# DcDc3V3.net
KiCad netlist of a schematic drawn in Altium Designer
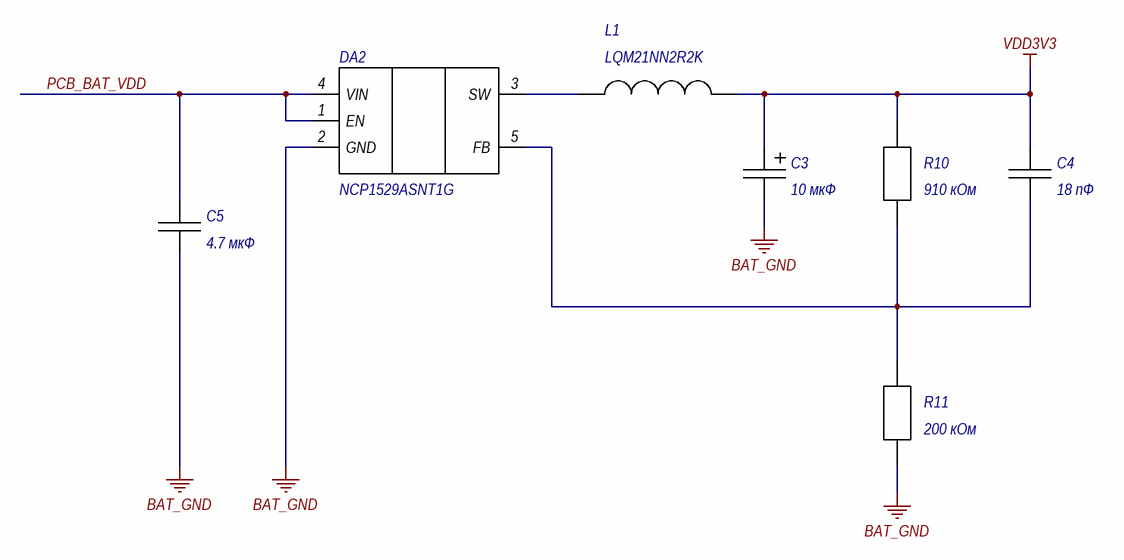
[diagram p0: DcDc3V3.SchDoc]

(export (version "E")
  (design (tool "Eeschema 10.0.6"))
  (components
    (comp (ref "C3")
      (value "10 мкФ")
      (footprint "C TAN_A")
      (description "SMD Tantalium Capacitor A")
      (libsource (lib "my_lib") (part "CAP TAN_A"))
    )
    (comp (ref "C4")
      (value "18 пФ")
      (footprint "C 0805")
      (description "SMD Capacitor 0805")
      (fields
        (field (name "TOLERANCE") "/Укажите допуск в процентах/")
        (field (name "MANUFACTURER") "/Укажите компанию-производителя/")
      )
      (libsource (lib "my_lib") (part "CAP 0805"))
    )
    (comp (ref "C5")
      (value "4.7 мкФ")
      (footprint "C 0805")
      (description "SMD Capacitor 0805")
      (fields
        (field (name "TOLERANCE") "/Укажите допуск в процентах/")
        (field (name "MANUFACTURER") "/Укажите компанию-производителя/")
      )
      (libsource (lib "my_lib") (part "CAP 0805"))
    )
    (comp (ref "DA2")
      (value "NCP1529ASNT1G")
      (footprint "TSOP-5")
      (libsource (lib "my_lib") (part "NCP1529ASNT1G"))
    )
    (comp (ref "L1")
      (value "LQM21NN2R2K")
      (footprint "LQM21N")
      (libsource (lib "my_lib") (part "LQM21NN2R2K"))
    )
    (comp (ref "R10") (value "910 кОм") (footprint "RES 0402") (libsource (lib "my_lib") (part "RES 0402")))
    (comp (ref "R11") (value "200 кОм") (footprint "RES 0402") (libsource (lib "my_lib") (part "RES 0402")))
  )
  (nets
    (net (code "1") (name "/PCB_BAT_VDD") (class "Default")
      (node (ref "C5") (pin "1") (pinfunction "1_1") (pintype "passive"))
      (node (ref "DA2") (pin "1") (pinfunction "EN_1") (pintype "passive"))
      (node (ref "DA2") (pin "4") (pinfunction "VIN_4") (pintype "passive"))
    )
    (net (code "2") (name "BAT_GND") (class "Default")
      (node (ref "C3") (pin "2") (pinfunction "2_2") (pintype "passive"))
      (node (ref "C5") (pin "2") (pinfunction "2_2") (pintype "passive"))
      (node (ref "DA2") (pin "2") (pinfunction "GND_2") (pintype "passive"))
      (node (ref "R11") (pin "2") (pinfunction "2_2") (pintype "passive"))
    )
    (net (code "3") (name "Net-(DA2-FB)") (class "Default")
      (node (ref "C4") (pin "2") (pinfunction "2_2") (pintype "passive"))
      (node (ref "DA2") (pin "5") (pinfunction "FB_5") (pintype "passive"))
      (node (ref "R10") (pin "1") (pinfunction "1_1") (pintype "passive"))
      (node (ref "R11") (pin "1") (pinfunction "1_1") (pintype "passive"))
    )
    (net (code "4") (name "Net-(DA2-SW)") (class "Default")
      (node (ref "DA2") (pin "3") (pinfunction "SW_3") (pintype "passive"))
      (node (ref "L1") (pin "1") (pinfunction "1_1") (pintype "passive"))
    )
    (net (code "5") (name "VDD3V3") (class "Default")
      (node (ref "C3") (pin "1") (pinfunction "1_1") (pintype "passive"))
      (node (ref "C4") (pin "1") (pinfunction "1_1") (pintype "passive"))
      (node (ref "L1") (pin "2") (pinfunction "2_2") (pintype "passive"))
      (node (ref "R10") (pin "2") (pinfunction "2_2") (pintype "passive"))
    )
  )
)
